# interface_hall.net
KiCad netlist of a schematic drawn in Altium Designer
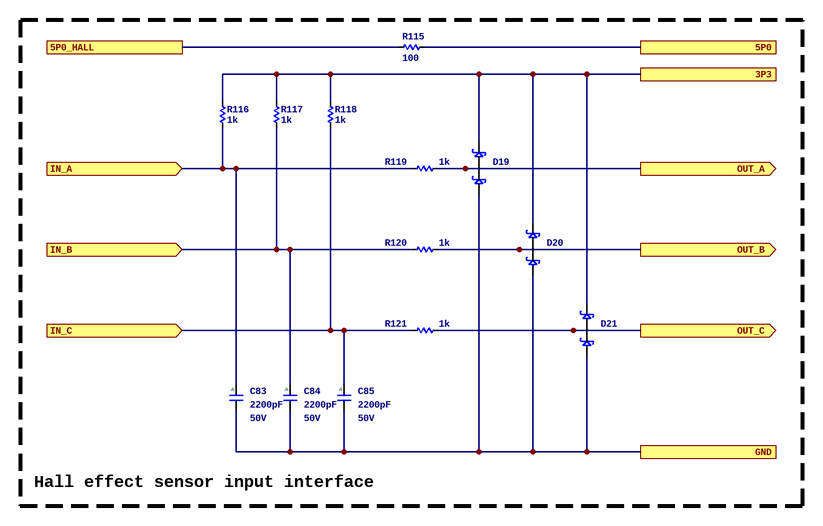
[diagram p0: interface_hall.SchDoc]

(export (version "E")
  (design (tool "Eeschema 10.0.6"))
  (components
    (comp (ref "C83")
      (value "CGA2B2X7R1H222M050BA")
      (footprint "C0402_0.55MM")
      (description "CAP CER 2200PF 50V X7R 0402")
      (fields
        (field (name "CAPACITANCE") "2200pF")
        (field (name "VOLTAGE - RATED") "50V")
        (field (name "TOLERANCE") "±20%")
        (field (name "MANUFACTURER") "TDK Corporation")
      )
      (libsource (lib "sscp") (part "__template_cap_auto"))
    )
    (comp (ref "C84")
      (value "CGA2B2X7R1H222M050BA")
      (footprint "C0402_0.55MM")
      (description "CAP CER 2200PF 50V X7R 0402")
      (fields
        (field (name "CAPACITANCE") "2200pF")
        (field (name "VOLTAGE - RATED") "50V")
        (field (name "TOLERANCE") "±20%")
        (field (name "MANUFACTURER") "TDK Corporation")
      )
      (libsource (lib "sscp") (part "__template_cap_auto"))
    )
    (comp (ref "C85")
      (value "CGA2B2X7R1H222M050BA")
      (footprint "C0402_0.55MM")
      (description "CAP CER 2200PF 50V X7R 0402")
      (fields
        (field (name "CAPACITANCE") "2200pF")
        (field (name "VOLTAGE - RATED") "50V")
        (field (name "TOLERANCE") "±20%")
        (field (name "MANUFACTURER") "TDK Corporation")
      )
      (libsource (lib "sscp") (part "__template_cap_auto"))
    )
    (comp (ref "D19")
      (value "BAT54SLT1G")
      (footprint "3SOT23")
      (description "DIODE SCHOTTKY DUAL 30V SOT23")
      (fields (field (name "MANUFACTURER") "ON Semiconductor"))
      (libsource (lib "SSCP") (part "SCHOTTKY_30V_DUAL_BAT54SLT1G"))
    )
    (comp (ref "D20")
      (value "BAT54SLT1G")
      (footprint "3SOT23")
      (description "DIODE SCHOTTKY DUAL 30V SOT23")
      (fields (field (name "MANUFACTURER") "ON Semiconductor"))
      (libsource (lib "SSCP") (part "SCHOTTKY_30V_DUAL_BAT54SLT1G"))
    )
    (comp (ref "D21")
      (value "BAT54SLT1G")
      (footprint "3SOT23")
      (description "DIODE SCHOTTKY DUAL 30V SOT23")
      (fields (field (name "MANUFACTURER") "ON Semiconductor"))
      (libsource (lib "SSCP") (part "SCHOTTKY_30V_DUAL_BAT54SLT1G"))
    )
    (comp (ref "R115")
      (value "ERJ-8ENF1000V")
      (footprint "R1206_0.70MM")
      (description "RES SMD 100 OHM 1% 1/4W 1206")
      (fields
        (field (name "RESISTANCE") "100")
        (field (name "TOLERANCE") "±1%")
        (field (name "MANUFACTURER") "Panasonic Electronic Components")
      )
      (libsource (lib "sscp") (part "__template_resistor"))
    )
    (comp (ref "R116")
      (value "~")
      (footprint "R0402_0.40MM")
      (description "RES SMD 1K OHM 1% 1/10W 0402")
      (fields (field (name "RESISTANCE") "1k") (field (name "TOLERANCE") "±1%"))
      (libsource (lib "sscp") (part "__template_resistor"))
    )
    (comp (ref "R117")
      (value "~")
      (footprint "R0402_0.40MM")
      (description "RES SMD 1K OHM 1% 1/10W 0402")
      (fields (field (name "RESISTANCE") "1k") (field (name "TOLERANCE") "±1%"))
      (libsource (lib "sscp") (part "__template_resistor"))
    )
    (comp (ref "R118")
      (value "~")
      (footprint "R0402_0.40MM")
      (description "RES SMD 1K OHM 1% 1/10W 0402")
      (fields (field (name "RESISTANCE") "1k") (field (name "TOLERANCE") "±1%"))
      (libsource (lib "sscp") (part "__template_resistor"))
    )
    (comp (ref "R119")
      (value "~")
      (footprint "R0402_0.40MM")
      (description "RES SMD 1K OHM 1% 1/10W 0402")
      (fields (field (name "RESISTANCE") "1k") (field (name "TOLERANCE") "±1%"))
      (libsource (lib "sscp") (part "__template_resistor"))
    )
    (comp (ref "R120")
      (value "~")
      (footprint "R0402_0.40MM")
      (description "RES SMD 1K OHM 1% 1/10W 0402")
      (fields (field (name "RESISTANCE") "1k") (field (name "TOLERANCE") "±1%"))
      (libsource (lib "sscp") (part "__template_resistor"))
    )
    (comp (ref "R121")
      (value "~")
      (footprint "R0402_0.40MM")
      (description "RES SMD 1K OHM 1% 1/10W 0402")
      (fields (field (name "RESISTANCE") "1k") (field (name "TOLERANCE") "±1%"))
      (libsource (lib "sscp") (part "__template_resistor"))
    )
  )
  (nets
    (net (code "1") (name "/3P3") (class "Default")
      (node (ref "D19") (pin "2") (pintype "passive"))
      (node (ref "D20") (pin "2") (pintype "passive"))
      (node (ref "D21") (pin "2") (pintype "passive"))
      (node (ref "R116") (pin "1") (pintype "passive"))
      (node (ref "R117") (pin "1") (pintype "passive"))
      (node (ref "R118") (pin "1") (pintype "passive"))
    )
    (net (code "2") (name "/5P0") (class "Default") (node (ref "R115") (pin "1") (pintype "passive")))
    (net (code "3") (name "/5P0_HALL") (class "Default") (node (ref "R115") (pin "2") (pintype "passive")))
    (net (code "4") (name "/GND") (class "Default")
      (node (ref "C83") (pin "2") (pintype "passive"))
      (node (ref "C84") (pin "2") (pintype "passive"))
      (node (ref "C85") (pin "2") (pintype "passive"))
      (node (ref "D19") (pin "1") (pintype "passive"))
      (node (ref "D20") (pin "1") (pintype "passive"))
      (node (ref "D21") (pin "1") (pintype "passive"))
    )
    (net (code "5") (name "/IN_A") (class "Default")
      (node (ref "C83") (pin "1") (pintype "passive"))
      (node (ref "R116") (pin "2") (pintype "passive"))
      (node (ref "R119") (pin "1") (pintype "passive"))
    )
    (net (code "6") (name "/IN_B") (class "Default")
      (node (ref "C84") (pin "1") (pintype "passive"))
      (node (ref "R117") (pin "2") (pintype "passive"))
      (node (ref "R120") (pin "1") (pintype "passive"))
    )
    (net (code "7") (name "/IN_C") (class "Default")
      (node (ref "C85") (pin "1") (pintype "passive"))
      (node (ref "R118") (pin "2") (pintype "passive"))
      (node (ref "R121") (pin "1") (pintype "passive"))
    )
    (net (code "8") (name "/OUT_A") (class "Default")
      (node (ref "D19") (pin "3") (pintype "passive"))
      (node (ref "R119") (pin "2") (pintype "passive"))
    )
    (net (code "9") (name "/OUT_B") (class "Default")
      (node (ref "D20") (pin "3") (pintype "passive"))
      (node (ref "R120") (pin "2") (pintype "passive"))
    )
    (net (code "10") (name "/OUT_C") (class "Default")
      (node (ref "D21") (pin "3") (pintype "passive"))
      (node (ref "R121") (pin "2") (pintype "passive"))
    )
  )
)
